# PowerSupply.net
KiCad netlist of a schematic drawn in Altium Designer
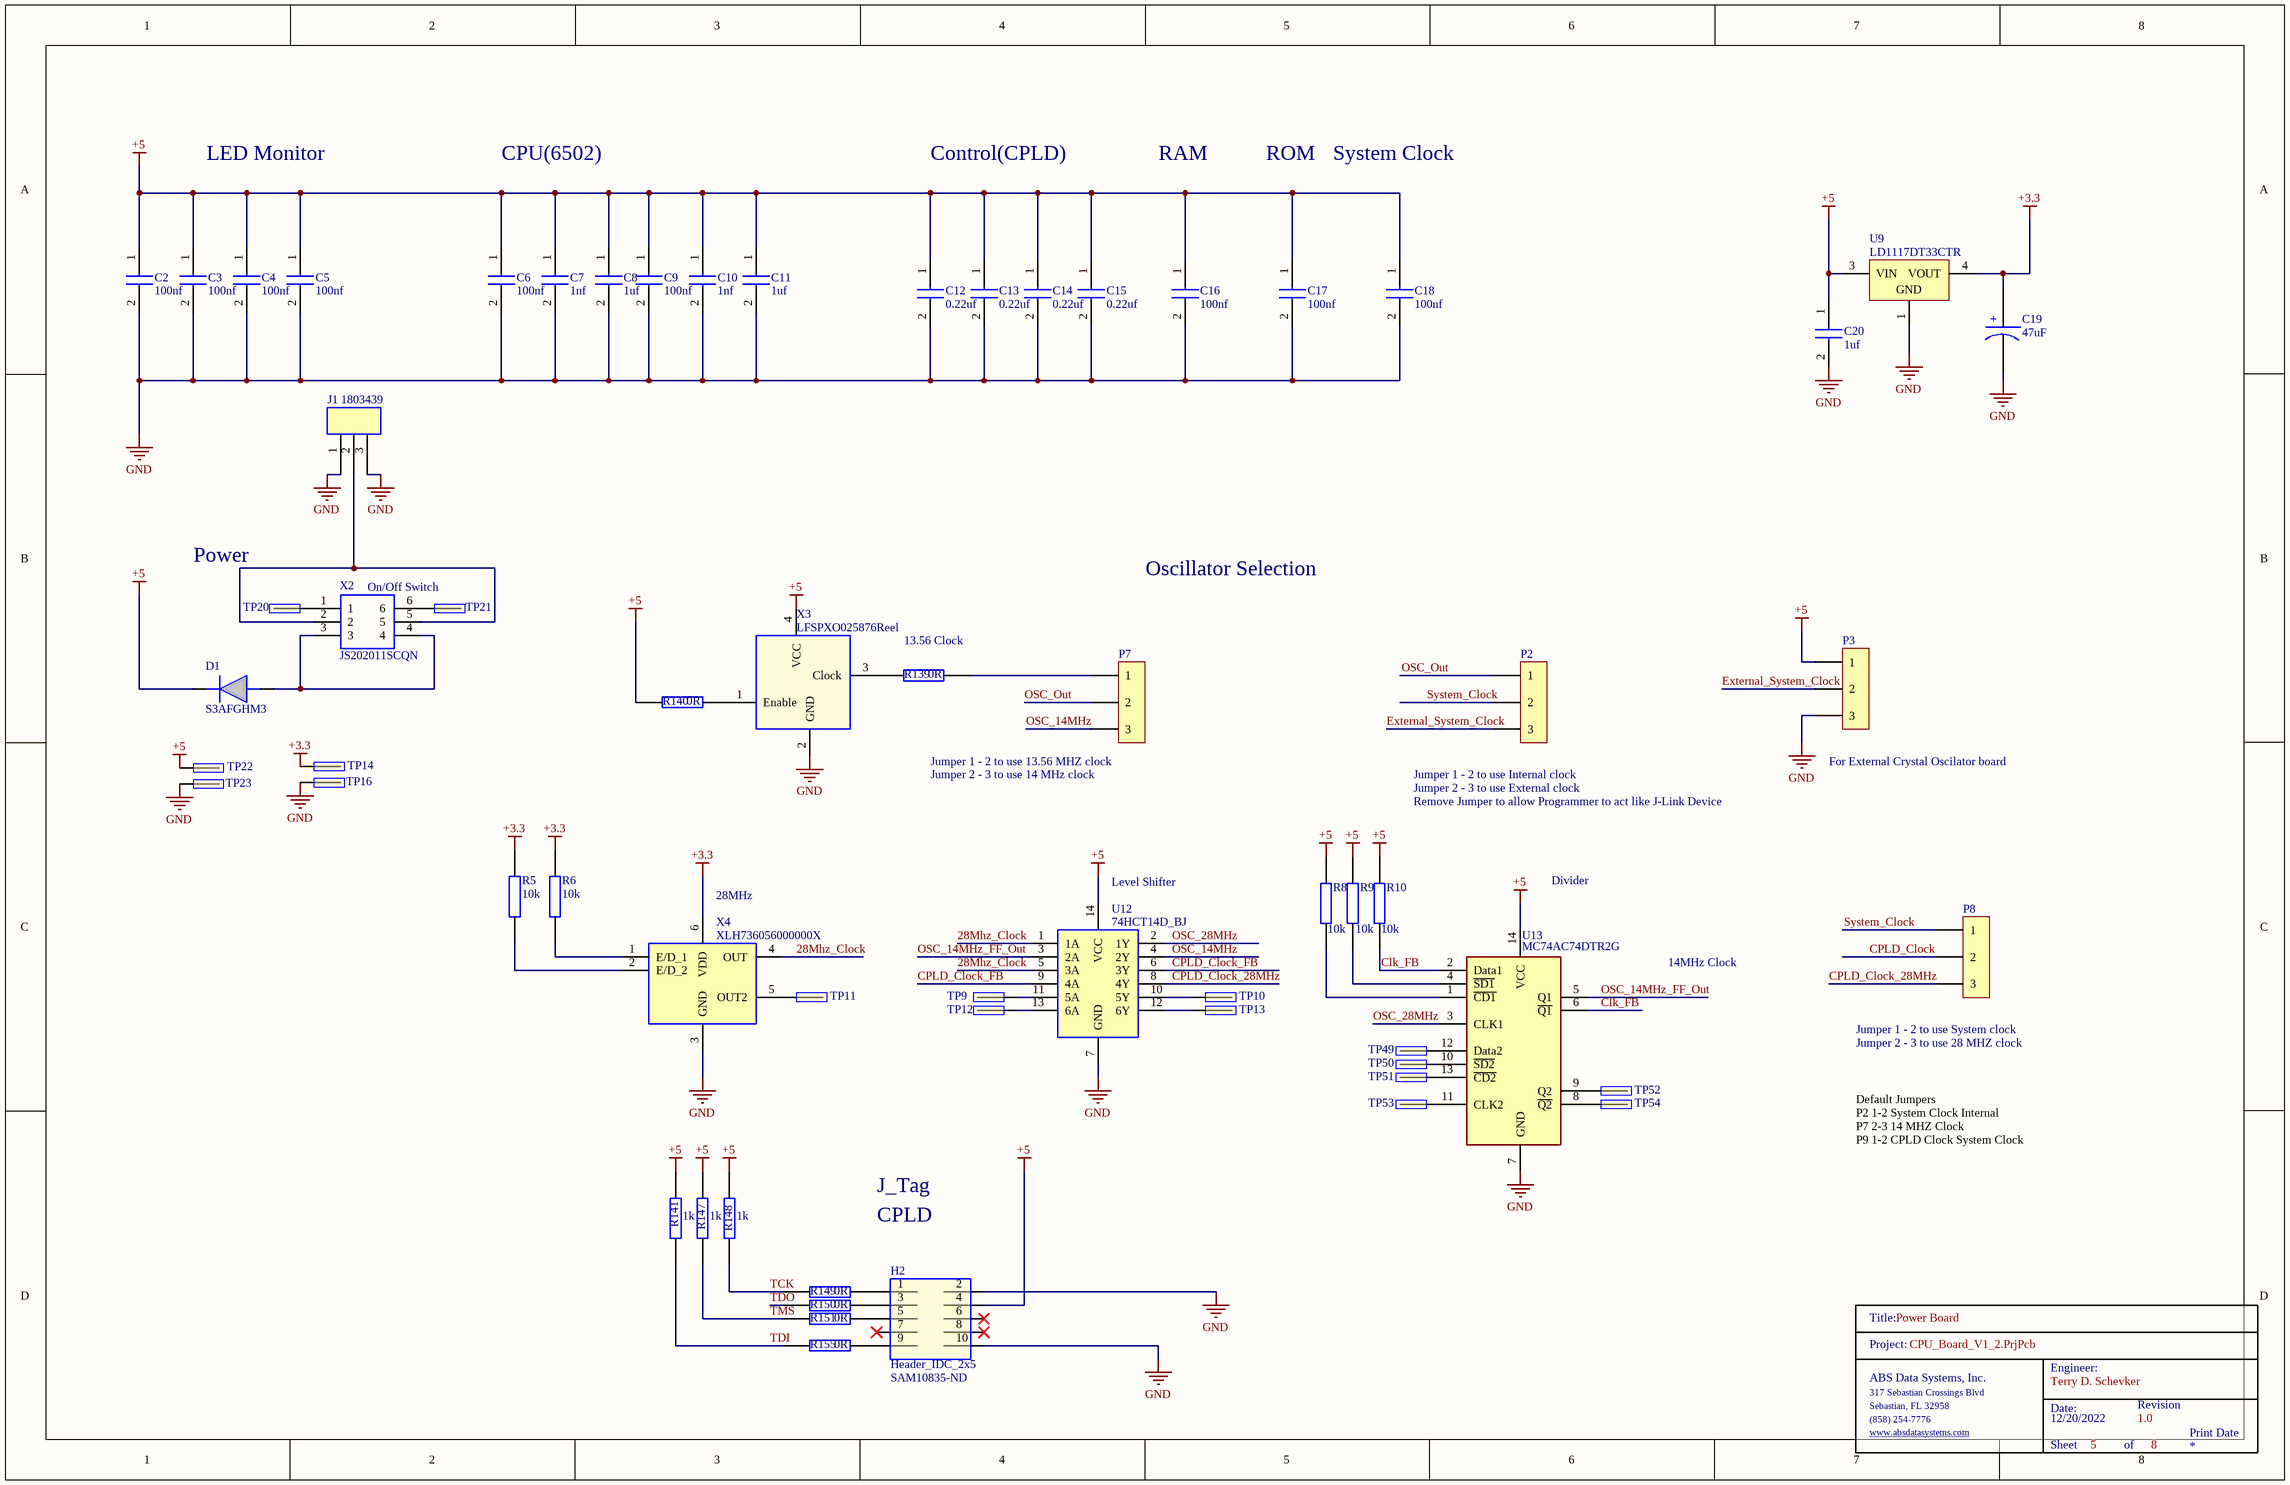
[diagram p0: PowerSupply.SchDoc]

(export (version "E")
  (design (tool "Eeschema 10.0.6"))
  (components
    (comp (ref "C2")
      (value "100nf")
      (footprint "0603")
      (description "Samsung Electro-Mechanics 0603 100nf")
      (libsource (lib "Capacitors") (part "CL10B104JB8NNNC"))
    )
    (comp (ref "C3")
      (value "100nf")
      (footprint "0603")
      (description "Samsung Electro-Mechanics 0603 100nf")
      (libsource (lib "Capacitors") (part "CL10B104JB8NNNC"))
    )
    (comp (ref "C4")
      (value "100nf")
      (footprint "0603")
      (description "Samsung Electro-Mechanics 0603 100nf")
      (libsource (lib "Capacitors") (part "CL10B104JB8NNNC"))
    )
    (comp (ref "C5")
      (value "100nf")
      (footprint "0603")
      (description "Samsung Electro-Mechanics 0603 100nf")
      (libsource (lib "Capacitors") (part "CL10B104JB8NNNC"))
    )
    (comp (ref "C6")
      (value "100nf")
      (footprint "0603")
      (description "Samsung Electro-Mechanics 0603 100nf")
      (libsource (lib "Capacitors") (part "CL10B104JB8NNNC"))
    )
    (comp (ref "C7")
      (value "1nf")
      (footprint "0603")
      (description "Samsung Electro-Mechanics 0603 1nf")
      (libsource (lib "Capacitors") (part "CL10B102KB8NNNL"))
    )
    (comp (ref "C8")
      (value "1uf")
      (footprint "0603")
      (description "Samsung Electro-Mechanics 0603 1uf")
      (libsource (lib "Capacitors") (part "CL10B105KA8NNNL"))
    )
    (comp (ref "C9")
      (value "100nf")
      (footprint "0603")
      (description "Samsung Electro-Mechanics 0603 100nf")
      (libsource (lib "Capacitors") (part "CL10B104JB8NNNC"))
    )
    (comp (ref "C10")
      (value "1nf")
      (footprint "0603")
      (description "Samsung Electro-Mechanics 0603 1nf")
      (libsource (lib "Capacitors") (part "CL10B102KB8NNNL"))
    )
    (comp (ref "C11")
      (value "1uf")
      (footprint "0603")
      (description "Samsung Electro-Mechanics 0603 1uf")
      (libsource (lib "Capacitors") (part "CL10B105KA8NNNL"))
    )
    (comp (ref "C12")
      (value "0.22uf")
      (footprint "0603")
      (description "Samsung Electro-Mechanics 0603 100nf")
      (libsource (lib "Capacitors") (part "CL10B104JB8NNNC"))
    )
    (comp (ref "C13")
      (value "0.22uf")
      (footprint "0603")
      (description "Samsung Electro-Mechanics 0603 100nf")
      (libsource (lib "Capacitors") (part "CL10B104JB8NNNC"))
    )
    (comp (ref "C14")
      (value "0.22uf")
      (footprint "0603")
      (description "Samsung Electro-Mechanics 0603 100nf")
      (libsource (lib "Capacitors") (part "CL10B104JB8NNNC"))
    )
    (comp (ref "C15")
      (value "0.22uf")
      (footprint "0603")
      (description "Samsung Electro-Mechanics 0603 100nf")
      (libsource (lib "Capacitors") (part "CL10B104JB8NNNC"))
    )
    (comp (ref "C16")
      (value "100nf")
      (footprint "0603")
      (description "Samsung Electro-Mechanics 0603 100nf")
      (libsource (lib "Capacitors") (part "CL10B104JB8NNNC"))
    )
    (comp (ref "C17")
      (value "100nf")
      (footprint "0603")
      (description "Samsung Electro-Mechanics 0603 100nf")
      (libsource (lib "Capacitors") (part "CL10B104JB8NNNC"))
    )
    (comp (ref "C18")
      (value "100nf")
      (footprint "0603")
      (description "Samsung Electro-Mechanics 0603 100nf")
      (libsource (lib "Capacitors") (part "CL10B104JB8NNNC"))
    )
    (comp (ref "C19")
      (value "47uF")
      (footprint "CapSMD_6.3x5.8")
      (description "CAP ALUM 47UF 20% 16V SMD")
      (fields
        (field (name "MANUFACTURER") "Nichicon")
        (field (name "MANUFACTURER PART NUMBER") "UUD1C470MCL1GS")
      )
      (libsource (lib "Capacitors") (part "UUD1C470MCL1GS"))
    )
    (comp (ref "C20")
      (value "1uf")
      (footprint "0603")
      (description "Samsung Electro-Mechanics 0603 1uf")
      (libsource (lib "Capacitors") (part "CL10B105KA8NNNL"))
    )
    (comp (ref "D1")
      (value "S3AFGHM3")
      (footprint "SemiConductors:do-221ac")
      (description "Rectifiers VR=400V, IO=3A")
      (fields
        (field (name "MOUSER PART NUMBER") "750-1N4001-G")
        (field (name "MANUFACTURER_PART_NUMBER") "1N4001-G")
      )
      (libsource (lib "SemiConductors") (part "S3AFGHM3/I"))
    )
    (comp (ref "H2")
      (value "Header_IDC_2x5")
      (footprint "HDR2X5")
      (description "10 Pin 2x5 Through Hold IDC Connector")
      (fields
        (field (name "MANUFACTURER") "Samtec")
        (field (name "MANUFACTURER PART NUMBER") "TST-105-01-G-D")
        (field (name "SUPPLIER PART NUMBER 1") "SAM10835-ND")
      )
      (libsource (lib "Misc") (part "Header_IDC_2x5"))
    )
    (comp (ref "J1")
      (value "1803439")
      (footprint "Connectors:1803439")
      (description "Connector")
      (fields (field (name "MOUSER PART NUMBER") "651-1803439"))
      (libsource (lib "Connectors") (part "1803439"))
    )
    (comp (ref "P2")
      (value "MHDR1X3_100")
      (footprint "MHDR1X3_100")
      (description "Header, 3-Pin")
      (fields (field (name "PUBLISHER") "Altium Limited"))
      (libsource (lib "Connectors") (part "MHDR1X3_100"))
    )
    (comp (ref "P3")
      (value "MHDR1X3_100")
      (footprint "MHDR1X3_100")
      (description "Header, 3-Pin")
      (fields (field (name "PUBLISHER") "Altium Limited"))
      (libsource (lib "Connectors") (part "MHDR1X3_100"))
    )
    (comp (ref "P7")
      (value "MHDR1X3_100")
      (footprint "MHDR1X3_100")
      (description "Header, 3-Pin")
      (fields (field (name "PUBLISHER") "Altium Limited"))
      (libsource (lib "Connectors") (part "MHDR1X3_100"))
    )
    (comp (ref "P8")
      (value "MHDR1X3_100")
      (footprint "MHDR1X3_100")
      (description "Header, 3-Pin")
      (fields (field (name "PUBLISHER") "Altium Limited"))
      (libsource (lib "Connectors") (part "MHDR1X3_100"))
    )
    (comp (ref "R5")
      (value "10k")
      (footprint "0603")
      (description "YAGEO 0603 10k ohm")
      (fields
        (field (name "MOUSER PART NUMBER") "603-RC0603JR-070RL")
        (field (name "MANUFACTURER_PART_NUMBER") "RC0603JR-070RL")
      )
      (libsource (lib "Resistors") (part "RC0603JR-0710KL"))
    )
    (comp (ref "R6")
      (value "10k")
      (footprint "0603")
      (description "YAGEO 0603 10k ohm")
      (fields
        (field (name "MOUSER PART NUMBER") "603-RC0603JR-070RL")
        (field (name "MANUFACTURER_PART_NUMBER") "RC0603JR-070RL")
      )
      (libsource (lib "Resistors") (part "RC0603JR-0710KL"))
    )
    (comp (ref "R8")
      (value "10k")
      (footprint "0603")
      (description "YAGEO 0603 10k ohm")
      (fields
        (field (name "MOUSER PART NUMBER") "603-RC0603JR-070RL")
        (field (name "MANUFACTURER_PART_NUMBER") "RC0603JR-070RL")
      )
      (libsource (lib "Resistors") (part "RC0603JR-0710KL"))
    )
    (comp (ref "R9")
      (value "10k")
      (footprint "0603")
      (description "YAGEO 0603 10k ohm")
      (fields
        (field (name "MOUSER PART NUMBER") "603-RC0603JR-070RL")
        (field (name "MANUFACTURER_PART_NUMBER") "RC0603JR-070RL")
      )
      (libsource (lib "Resistors") (part "RC0603JR-0710KL"))
    )
    (comp (ref "R10")
      (value "10k")
      (footprint "0603")
      (description "YAGEO 0603 10k ohm")
      (fields
        (field (name "MOUSER PART NUMBER") "603-RC0603JR-070RL")
        (field (name "MANUFACTURER_PART_NUMBER") "RC0603JR-070RL")
      )
      (libsource (lib "Resistors") (part "RC0603JR-0710KL"))
    )
    (comp (ref "R139")
      (value "0R")
      (footprint "0603")
      (description "YAGEO 0603 0 ohm")
      (fields
        (field (name "MOUSER PART NUMBER") "603-RC0603JR-070RL")
        (field (name "MANUFACTURER_PART_NUMBER") "RC0603JR-070RL")
      )
      (libsource (lib "Resistors") (part "RC0603JR-070RL"))
    )
    (comp (ref "R140")
      (value "0R")
      (footprint "0603")
      (description "YAGEO 0603 0 ohm")
      (fields
        (field (name "MOUSER PART NUMBER") "603-RC0603JR-070RL")
        (field (name "MANUFACTURER_PART_NUMBER") "RC0603JR-070RL")
      )
      (libsource (lib "Resistors") (part "RC0603JR-070RL"))
    )
    (comp (ref "R141")
      (value "1k")
      (footprint "0603")
      (description "YAGEO 0603 1k ohm")
      (fields
        (field (name "MOUSER PART NUMBER") "603-RC0603JR-070RL")
        (field (name "MANUFACTURER_PART_NUMBER") "RC0603JR-070RL")
      )
      (libsource (lib "Resistors") (part "AC0603FR-7W1KL"))
    )
    (comp (ref "R147")
      (value "1k")
      (footprint "0603")
      (description "YAGEO 0603 1k ohm")
      (fields
        (field (name "MOUSER PART NUMBER") "603-RC0603JR-070RL")
        (field (name "MANUFACTURER_PART_NUMBER") "RC0603JR-070RL")
      )
      (libsource (lib "Resistors") (part "AC0603FR-7W1KL"))
    )
    (comp (ref "R148")
      (value "1k")
      (footprint "0603")
      (description "YAGEO 0603 1k ohm")
      (fields
        (field (name "MOUSER PART NUMBER") "603-RC0603JR-070RL")
        (field (name "MANUFACTURER_PART_NUMBER") "RC0603JR-070RL")
      )
      (libsource (lib "Resistors") (part "AC0603FR-7W1KL"))
    )
    (comp (ref "R149")
      (value "0R")
      (footprint "0603")
      (description "YAGEO 0603 0 ohm")
      (fields
        (field (name "MOUSER PART NUMBER") "603-RC0603JR-070RL")
        (field (name "MANUFACTURER_PART_NUMBER") "RC0603JR-070RL")
      )
      (libsource (lib "Resistors") (part "RC0603JR-070RL"))
    )
    (comp (ref "R150")
      (value "0R")
      (footprint "0603")
      (description "YAGEO 0603 0 ohm")
      (fields
        (field (name "MOUSER PART NUMBER") "603-RC0603JR-070RL")
        (field (name "MANUFACTURER_PART_NUMBER") "RC0603JR-070RL")
      )
      (libsource (lib "Resistors") (part "RC0603JR-070RL"))
    )
    (comp (ref "R151")
      (value "0R")
      (footprint "0603")
      (description "YAGEO 0603 0 ohm")
      (fields
        (field (name "MOUSER PART NUMBER") "603-RC0603JR-070RL")
        (field (name "MANUFACTURER_PART_NUMBER") "RC0603JR-070RL")
      )
      (libsource (lib "Resistors") (part "RC0603JR-070RL"))
    )
    (comp (ref "R155")
      (value "0R")
      (footprint "0603")
      (description "YAGEO 0603 0 ohm")
      (fields
        (field (name "MOUSER PART NUMBER") "603-RC0603JR-070RL")
        (field (name "MANUFACTURER_PART_NUMBER") "RC0603JR-070RL")
      )
      (libsource (lib "Resistors") (part "RC0603JR-070RL"))
    )
    (comp (ref "TitleBlock_3") (value "TitleBlock") (libsource (lib "Misc") (part "TitleBlock")))
    (comp (ref "TP9")
      (value "~")
      (footprint "TP")
      (fields
        (field (name "MANUFACTURER") "Samtec")
        (field (name "MANUFACTURER PART NUMBER") "TST-105-01-G-D")
      )
      (libsource (lib "Misc") (part "TP"))
    )
    (comp (ref "TP10")
      (value "TP")
      (footprint "TP")
      (fields
        (field (name "MANUFACTURER") "Samtec")
        (field (name "MANUFACTURER PART NUMBER") "TST-105-01-G-D")
      )
      (libsource (lib "") (part "TP_1"))
    )
    (comp (ref "TP11")
      (value "TP")
      (footprint "TP")
      (fields
        (field (name "MANUFACTURER") "Samtec")
        (field (name "MANUFACTURER PART NUMBER") "TST-105-01-G-D")
      )
      (libsource (lib "") (part "TP_1"))
    )
    (comp (ref "TP12")
      (value "~")
      (footprint "TP")
      (fields
        (field (name "MANUFACTURER") "Samtec")
        (field (name "MANUFACTURER PART NUMBER") "TST-105-01-G-D")
      )
      (libsource (lib "Misc") (part "TP"))
    )
    (comp (ref "TP13")
      (value "TP")
      (footprint "TP")
      (fields
        (field (name "MANUFACTURER") "Samtec")
        (field (name "MANUFACTURER PART NUMBER") "TST-105-01-G-D")
      )
      (libsource (lib "") (part "TP_1"))
    )
    (comp (ref "TP14")
      (value "TP")
      (footprint "TP")
      (fields
        (field (name "MANUFACTURER") "Samtec")
        (field (name "MANUFACTURER PART NUMBER") "TST-105-01-G-D")
      )
      (libsource (lib "") (part "TP_2"))
    )
    (comp (ref "TP16")
      (value "TP")
      (footprint "TP")
      (fields
        (field (name "MANUFACTURER") "Samtec")
        (field (name "MANUFACTURER PART NUMBER") "TST-105-01-G-D")
      )
      (libsource (lib "") (part "TP_2"))
    )
    (comp (ref "TP20")
      (value "~")
      (footprint "TP")
      (fields
        (field (name "MANUFACTURER") "Samtec")
        (field (name "MANUFACTURER PART NUMBER") "TST-105-01-G-D")
      )
      (libsource (lib "Misc") (part "TP"))
    )
    (comp (ref "TP21")
      (value "~")
      (footprint "TP")
      (fields
        (field (name "MANUFACTURER") "Samtec")
        (field (name "MANUFACTURER PART NUMBER") "TST-105-01-G-D")
      )
      (libsource (lib "") (part "TP_2"))
    )
    (comp (ref "TP22")
      (value "TP")
      (footprint "TP")
      (fields
        (field (name "MANUFACTURER") "Samtec")
        (field (name "MANUFACTURER PART NUMBER") "TST-105-01-G-D")
      )
      (libsource (lib "") (part "TP_2"))
    )
    (comp (ref "TP23")
      (value "TP")
      (footprint "TP")
      (fields
        (field (name "MANUFACTURER") "Samtec")
        (field (name "MANUFACTURER PART NUMBER") "TST-105-01-G-D")
      )
      (libsource (lib "") (part "TP_2"))
    )
    (comp (ref "TP49")
      (value "TP")
      (footprint "TP")
      (fields
        (field (name "MANUFACTURER") "Samtec")
        (field (name "MANUFACTURER PART NUMBER") "TST-105-01-G-D")
      )
      (libsource (lib "Misc") (part "TP"))
    )
    (comp (ref "TP50")
      (value "TP")
      (footprint "TP")
      (fields
        (field (name "MANUFACTURER") "Samtec")
        (field (name "MANUFACTURER PART NUMBER") "TST-105-01-G-D")
      )
      (libsource (lib "Misc") (part "TP"))
    )
    (comp (ref "TP51")
      (value "TP")
      (footprint "TP")
      (fields
        (field (name "MANUFACTURER") "Samtec")
        (field (name "MANUFACTURER PART NUMBER") "TST-105-01-G-D")
      )
      (libsource (lib "Misc") (part "TP"))
    )
    (comp (ref "TP52")
      (value "TP")
      (footprint "TP")
      (fields
        (field (name "MANUFACTURER") "Samtec")
        (field (name "MANUFACTURER PART NUMBER") "TST-105-01-G-D")
      )
      (libsource (lib "") (part "TP_1"))
    )
    (comp (ref "TP53")
      (value "TP")
      (footprint "TP")
      (fields
        (field (name "MANUFACTURER") "Samtec")
        (field (name "MANUFACTURER PART NUMBER") "TST-105-01-G-D")
      )
      (libsource (lib "Misc") (part "TP"))
    )
    (comp (ref "TP54")
      (value "TP")
      (footprint "TP")
      (fields
        (field (name "MANUFACTURER") "Samtec")
        (field (name "MANUFACTURER PART NUMBER") "TST-105-01-G-D")
      )
      (libsource (lib "") (part "TP_1"))
    )
    (comp (ref "U9")
      (value "LD1117DT33CTR")
      (footprint "TO-252_N")
      (description "3.3V Voltage Regulator SMD")
      (libsource (lib "Misc") (part "PM-REG-LD1117-SOT3"))
    )
    (comp (ref "U12")
      (value "74HCT14D_BJ")
      (footprint "Logic:SOIC127P600X175-14N")
      (description "Inveter")
      (libsource (lib "Logic") (part "74HCT14D_BJ"))
    )
    (comp (ref "U13")
      (value "MC74AC74DTR2G")
      (footprint "Logic:SOP65P640X120-14N")
      (description "FlipFlop")
      (libsource (lib "Logic") (part "MC74AC74DTR2G"))
    )
    (comp (ref "X2")
      (value "JS202011SCQN")
      (footprint "JS202011SCQN")
      (description "Sub miniature slide switches")
      (fields (field (name "MOUSER PART NUMBER") "611-JS202011SCQN"))
      (libsource (lib "Misc") (part "JS202011SCQN"))
    )
    (comp (ref "X3")
      (value "LFSPXO025876Reel")
      (footprint "LFSPXO025876Reel")
      (description "Standard Clock Oscillators 13.56MHz 5V 100ppm -40C +85C")
      (fields (field (name "MOUSER PART NUMBER") "449-LFSPXO025876REEL"))
      (libsource (lib "Misc") (part "LFSPXO025876Reel"))
    )
    (comp (ref "X4")
      (value "XLH736056000000X")
      (footprint "Misc:XLH736056000000X")
      (description "Crystall Oscillator")
      (libsource (lib "Misc") (part "XLH736056000000X"))
    )
  )
  (nets
    (net (code "1") (name "+3.3") (class "Default")
      (node (ref "C19") (pin "1") (pinfunction "1_1") (pintype "passive"))
      (node (ref "R5") (pin "2") (pinfunction "2_2") (pintype "passive"))
      (node (ref "R6") (pin "2") (pinfunction "2_2") (pintype "passive"))
      (node (ref "TP14") (pin "1") (pinfunction "1_1") (pintype "passive"))
      (node (ref "U9") (pin "4") (pinfunction "VOUT_4") (pintype "power_in"))
      (node (ref "X4") (pin "6") (pinfunction "VDD_6") (pintype "passive"))
    )
    (net (code "2") (name "+5") (class "Default")
      (node (ref "C10") (pin "1") (pinfunction "1_1") (pintype "passive"))
      (node (ref "C11") (pin "1") (pinfunction "1_1") (pintype "passive"))
      (node (ref "C12") (pin "1") (pinfunction "1_1") (pintype "passive"))
      (node (ref "C13") (pin "1") (pinfunction "1_1") (pintype "passive"))
      (node (ref "C14") (pin "1") (pinfunction "1_1") (pintype "passive"))
      (node (ref "C15") (pin "1") (pinfunction "1_1") (pintype "passive"))
      (node (ref "C16") (pin "1") (pinfunction "1_1") (pintype "passive"))
      (node (ref "C17") (pin "1") (pinfunction "1_1") (pintype "passive"))
      (node (ref "C18") (pin "1") (pinfunction "1_1") (pintype "passive"))
      (node (ref "C2") (pin "1") (pinfunction "1_1") (pintype "passive"))
      (node (ref "C20") (pin "1") (pinfunction "1_1") (pintype "passive"))
      (node (ref "C3") (pin "1") (pinfunction "1_1") (pintype "passive"))
      (node (ref "C4") (pin "1") (pinfunction "1_1") (pintype "passive"))
      (node (ref "C5") (pin "1") (pinfunction "1_1") (pintype "passive"))
      (node (ref "C6") (pin "1") (pinfunction "1_1") (pintype "passive"))
      (node (ref "C7") (pin "1") (pinfunction "1_1") (pintype "passive"))
      (node (ref "C8") (pin "1") (pinfunction "1_1") (pintype "passive"))
      (node (ref "C9") (pin "1") (pinfunction "1_1") (pintype "passive"))
      (node (ref "D1") (pin "1") (pinfunction "K_1") (pintype "passive"))
      (node (ref "H2") (pin "4") (pinfunction "4_4") (pintype "passive"))
      (node (ref "P3") (pin "1") (pinfunction "1_1") (pintype "passive"))
      (node (ref "R10") (pin "2") (pinfunction "2_2") (pintype "passive"))
      (node (ref "R140") (pin "1") (pinfunction "1_1") (pintype "passive"))
      (node (ref "R141") (pin "1") (pinfunction "1_1") (pintype "passive"))
      (node (ref "R147") (pin "1") (pinfunction "1_1") (pintype "passive"))
      (node (ref "R148") (pin "1") (pinfunction "1_1") (pintype "passive"))
      (node (ref "R8") (pin "2") (pinfunction "2_2") (pintype "passive"))
      (node (ref "R9") (pin "2") (pinfunction "2_2") (pintype "passive"))
      (node (ref "TP22") (pin "1") (pinfunction "1_1") (pintype "passive"))
      (node (ref "U12") (pin "14") (pinfunction "VCC_14") (pintype "passive"))
      (node (ref "U13") (pin "14") (pinfunction "VCC_14") (pintype "passive"))
      (node (ref "U9") (pin "3") (pinfunction "VIN_3") (pintype "power_in"))
      (node (ref "X3") (pin "4") (pinfunction "VCC_4") (pintype "passive"))
    )
    (net (code "3") (name "/28Mhz_Clock") (class "Default")
      (node (ref "U12") (pin "1") (pinfunction "1A_1") (pintype "passive"))
      (node (ref "U12") (pin "5") (pinfunction "3A_5") (pintype "passive"))
      (node (ref "X4") (pin "4") (pinfunction "OUT_4") (pintype "passive"))
    )
    (net (code "4") (name "/CPLD_Clock") (class "Default")
      (node (ref "P8") (pin "2") (pinfunction "2_2") (pintype "passive"))
    )
    (net (code "5") (name "/CPLD_Clock_28MHz") (class "Default")
      (node (ref "P8") (pin "3") (pinfunction "3_3") (pintype "passive"))
      (node (ref "U12") (pin "8") (pinfunction "4Y_8") (pintype "passive"))
    )
    (net (code "6") (name "/CPLD_Clock_FB") (class "Default")
      (node (ref "U12") (pin "6") (pinfunction "3Y_6") (pintype "passive"))
      (node (ref "U12") (pin "9") (pinfunction "4A_9") (pintype "passive"))
    )
    (net (code "7") (name "/Clk_FB") (class "Default")
      (node (ref "R10") (pin "1") (pinfunction "1_1") (pintype "passive"))
      (node (ref "U13") (pin "2") (pinfunction "Data1_2") (pintype "passive"))
      (node (ref "U13") (pin "6") (pinfunction "~{Q1}_6") (pintype "passive"))
    )
    (net (code "8") (name "/External_System_Clock") (class "Default")
      (node (ref "P2") (pin "3") (pinfunction "3_3") (pintype "passive"))
      (node (ref "P3") (pin "2") (pinfunction "2_2") (pintype "passive"))
    )
    (net (code "9") (name "/OSC_14MHz") (class "Default")
      (node (ref "P7") (pin "3") (pinfunction "3_3") (pintype "passive"))
      (node (ref "U12") (pin "4") (pinfunction "2Y_4") (pintype "passive"))
    )
    (net (code "10") (name "/OSC_14MHz_FF_Out") (class "Default")
      (node (ref "U12") (pin "3") (pinfunction "2A_3") (pintype "passive"))
      (node (ref "U13") (pin "5") (pinfunction "Q1_5") (pintype "passive"))
    )
    (net (code "11") (name "/OSC_28MHz") (class "Default")
      (node (ref "U12") (pin "2") (pinfunction "1Y_2") (pintype "passive"))
      (node (ref "U13") (pin "3") (pinfunction "CLK1_3") (pintype "passive"))
    )
    (net (code "12") (name "/OSC_Out") (class "Default")
      (node (ref "P2") (pin "1") (pinfunction "1_1") (pintype "passive"))
      (node (ref "P7") (pin "2") (pinfunction "2_2") (pintype "passive"))
    )
    (net (code "13") (name "/System_Clock") (class "Default")
      (node (ref "P2") (pin "2") (pinfunction "2_2") (pintype "passive"))
      (node (ref "P8") (pin "1") (pinfunction "1_1") (pintype "passive"))
    )
    (net (code "14") (name "/TCK") (class "Default")
      (node (ref "R148") (pin "2") (pinfunction "2_2") (pintype "passive"))
      (node (ref "R149") (pin "1") (pinfunction "1_1") (pintype "passive"))
    )
    (net (code "15") (name "/TDI") (class "Default")
      (node (ref "R141") (pin "2") (pinfunction "2_2") (pintype "passive"))
      (node (ref "R155") (pin "1") (pinfunction "1_1") (pintype "passive"))
    )
    (net (code "16") (name "/TDO") (class "Default")
      (node (ref "R150") (pin "1") (pinfunction "1_1") (pintype "passive"))
    )
    (net (code "17") (name "/TMS") (class "Default")
      (node (ref "R147") (pin "2") (pinfunction "2_2") (pintype "passive"))
      (node (ref "R151") (pin "1") (pinfunction "1_1") (pintype "passive"))
    )
    (net (code "18") (name "GND") (class "Default")
      (node (ref "C10") (pin "2") (pinfunction "2_2") (pintype "passive"))
      (node (ref "C11") (pin "2") (pinfunction "2_2") (pintype "passive"))
      (node (ref "C12") (pin "2") (pinfunction "2_2") (pintype "passive"))
      (node (ref "C13") (pin "2") (pinfunction "2_2") (pintype "passive"))
      (node (ref "C14") (pin "2") (pinfunction "2_2") (pintype "passive"))
      (node (ref "C15") (pin "2") (pinfunction "2_2") (pintype "passive"))
      (node (ref "C16") (pin "2") (pinfunction "2_2") (pintype "passive"))
      (node (ref "C17") (pin "2") (pinfunction "2_2") (pintype "passive"))
      (node (ref "C18") (pin "2") (pinfunction "2_2") (pintype "passive"))
      (node (ref "C19") (pin "2") (pinfunction "2_2") (pintype "passive"))
      (node (ref "C2") (pin "2") (pinfunction "2_2") (pintype "passive"))
      (node (ref "C20") (pin "2") (pinfunction "2_2") (pintype "passive"))
      (node (ref "C3") (pin "2") (pinfunction "2_2") (pintype "passive"))
      (node (ref "C4") (pin "2") (pinfunction "2_2") (pintype "passive"))
      (node (ref "C5") (pin "2") (pinfunction "2_2") (pintype "passive"))
      (node (ref "C6") (pin "2") (pinfunction "2_2") (pintype "passive"))
      (node (ref "C7") (pin "2") (pinfunction "2_2") (pintype "passive"))
      (node (ref "C8") (pin "2") (pinfunction "2_2") (pintype "passive"))
      (node (ref "C9") (pin "2") (pinfunction "2_2") (pintype "passive"))
      (node (ref "H2") (pin "10") (pinfunction "10_10") (pintype "passive"))
      (node (ref "H2") (pin "2") (pinfunction "2_2") (pintype "passive"))
      (node (ref "J1") (pin "1") (pinfunction "1_1") (pintype "passive"))
      (node (ref "J1") (pin "3") (pinfunction "3_3") (pintype "passive"))
      (node (ref "P3") (pin "3") (pinfunction "3_3") (pintype "passive"))
      (node (ref "TP16") (pin "1") (pinfunction "1_1") (pintype "passive"))
      (node (ref "TP23") (pin "1") (pinfunction "1_1") (pintype "passive"))
      (node (ref "U12") (pin "7") (pinfunction "GND_7") (pintype "passive"))
      (node (ref "U13") (pin "7") (pinfunction "GND_7") (pintype "passive"))
      (node (ref "U9") (pin "1") (pinfunction "GND_1") (pintype "power_in"))
      (node (ref "X3") (pin "2") (pinfunction "GND_2") (pintype "passive"))
      (node (ref "X4") (pin "3") (pinfunction "GND_3") (pintype "passive"))
    )
    (net (code "19") (name "Net-(D1-A)") (class "Default")
      (node (ref "D1") (pin "2") (pinfunction "A_2") (pintype "passive"))
      (node (ref "X2") (pin "3") (pinfunction "3_3") (pintype "passive"))
      (node (ref "X2") (pin "4") (pinfunction "4_4") (pintype "passive"))
    )
    (net (code "20") (name "Net-(H2-Pad1)") (class "Default")
      (node (ref "H2") (pin "1") (pinfunction "1_1") (pintype "passive"))
      (node (ref "R149") (pin "2") (pinfunction "2_2") (pintype "passive"))
    )
    (net (code "21") (name "Net-(H2-Pad3)") (class "Default")
      (node (ref "H2") (pin "3") (pinfunction "3_3") (pintype "passive"))
      (node (ref "R150") (pin "2") (pinfunction "2_2") (pintype "passive"))
    )
    (net (code "22") (name "Net-(H2-Pad5)") (class "Default")
      (node (ref "H2") (pin "5") (pinfunction "5_5") (pintype "passive"))
      (node (ref "R151") (pin "2") (pinfunction "2_2") (pintype "passive"))
    )
    (net (code "23") (name "Net-(H2-Pad9)") (class "Default")
      (node (ref "H2") (pin "9") (pinfunction "9_9") (pintype "passive"))
      (node (ref "R155") (pin "2") (pinfunction "2_2") (pintype "passive"))
    )
    (net (code "24") (name "Net-(J1-Pad2)") (class "Default")
      (node (ref "J1") (pin "2") (pinfunction "2_2") (pintype "passive"))
      (node (ref "X2") (pin "2") (pinfunction "2_2") (pintype "passive"))
      (node (ref "X2") (pin "5") (pinfunction "5_5") (pintype "passive"))
    )
    (net (code "25") (name "Net-(P7-Pad1)") (class "Default")
      (node (ref "P7") (pin "1") (pinfunction "1_1") (pintype "passive"))
      (node (ref "R139") (pin "2") (pinfunction "2_2") (pintype "passive"))
    )
    (net (code "26") (name "Net-(TP20-Pad1)") (class "Default")
      (node (ref "TP20") (pin "1") (pinfunction "1_1") (pintype "passive"))
      (node (ref "X2") (pin "1") (pinfunction "1_1") (pintype "passive"))
    )
    (net (code "27") (name "Net-(TP21-Pad1)") (class "Default")
      (node (ref "TP21") (pin "1") (pinfunction "1_1") (pintype "passive"))
      (node (ref "X2") (pin "6") (pinfunction "6_6") (pintype "passive"))
    )
    (net (code "28") (name "Net-(U12-5A)") (class "Default")
      (node (ref "TP9") (pin "1") (pinfunction "1_1") (pintype "passive"))
      (node (ref "U12") (pin "11") (pinfunction "5A_11") (pintype "passive"))
    )
    (net (code "29") (name "Net-(U12-5Y)") (class "Default")
      (node (ref "TP10") (pin "1") (pinfunction "1_1") (pintype "passive"))
      (node (ref "U12") (pin "10") (pinfunction "5Y_10") (pintype "passive"))
    )
    (net (code "30") (name "Net-(U12-6A)") (class "Default")
      (node (ref "TP12") (pin "1") (pinfunction "1_1") (pintype "passive"))
      (node (ref "U12") (pin "13") (pinfunction "6A_13") (pintype "passive"))
    )
    (net (code "31") (name "Net-(U12-6Y)") (class "Default")
      (node (ref "TP13") (pin "1") (pinfunction "1_1") (pintype "passive"))
      (node (ref "U12") (pin "12") (pinfunction "6Y_12") (pintype "passive"))
    )
    (net (code "32") (name "Net-(U13-CLK2)") (class "Default")
      (node (ref "TP53") (pin "1") (pinfunction "1_1") (pintype "passive"))
      (node (ref "U13") (pin "11") (pinfunction "CLK2_11") (pintype "passive"))
    )
    (net (code "33") (name "Net-(U13-Data2)") (class "Default")
      (node (ref "TP49") (pin "1") (pinfunction "1_1") (pintype "passive"))
      (node (ref "U13") (pin "12") (pinfunction "Data2_12") (pintype "passive"))
    )
    (net (code "34") (name "Net-(U13-Q2)") (class "Default")
      (node (ref "TP52") (pin "1") (pinfunction "1_1") (pintype "passive"))
      (node (ref "U13") (pin "9") (pinfunction "Q2_9") (pintype "passive"))
    )
    (net (code "35") (name "Net-(U13-~{CD1})") (class "Default")
      (node (ref "R8") (pin "1") (pinfunction "1_1") (pintype "passive"))
      (node (ref "U13") (pin "1") (pinfunction "~{CD1}_1") (pintype "passive"))
    )
    (net (code "36") (name "Net-(U13-~{CD2})") (class "Default")
      (node (ref "TP51") (pin "1") (pinfunction "1_1") (pintype "passive"))
      (node (ref "U13") (pin "13") (pinfunction "~{CD2}_13") (pintype "passive"))
    )
    (net (code "37") (name "Net-(U13-~{Q2})") (class "Default")
      (node (ref "TP54") (pin "1") (pinfunction "1_1") (pintype "passive"))
      (node (ref "U13") (pin "8") (pinfunction "~{Q2}_8") (pintype "passive"))
    )
    (net (code "38") (name "Net-(U13-~{SD1})") (class "Default")
      (node (ref "R9") (pin "1") (pinfunction "1_1") (pintype "passive"))
      (node (ref "U13") (pin "4") (pinfunction "~{SD1}_4") (pintype "passive"))
    )
    (net (code "39") (name "Net-(U13-~{SD2})") (class "Default")
      (node (ref "TP50") (pin "1") (pinfunction "1_1") (pintype "passive"))
      (node (ref "U13") (pin "10") (pinfunction "~{SD2}_10") (pintype "passive"))
    )
    (net (code "40") (name "Net-(X3-Clock)") (class "Default")
      (node (ref "R139") (pin "1") (pinfunction "1_1") (pintype "passive"))
      (node (ref "X3") (pin "3") (pinfunction "Clock_3") (pintype "passive"))
    )
    (net (code "41") (name "Net-(X3-Enable)") (class "Default")
      (node (ref "R140") (pin "2") (pinfunction "2_2") (pintype "passive"))
      (node (ref "X3") (pin "1") (pinfunction "Enable_1") (pintype "passive"))
    )
    (net (code "42") (name "Net-(X4-E{slash}D_1)") (class "Default")
      (node (ref "R6") (pin "1") (pinfunction "1_1") (pintype "passive"))
      (node (ref "X4") (pin "1") (pinfunction "E/D_1_1") (pintype "passive"))
    )
    (net (code "43") (name "Net-(X4-E{slash}D_2)") (class "Default")
      (node (ref "R5") (pin "1") (pinfunction "1_1") (pintype "passive"))
      (node (ref "X4") (pin "2") (pinfunction "E/D_2_2") (pintype "passive"))
    )
    (net (code "44") (name "Net-(X4-OUT2)") (class "Default")
      (node (ref "TP11") (pin "1") (pinfunction "1_1") (pintype "passive"))
      (node (ref "X4") (pin "5") (pinfunction "OUT2_5") (pintype "passive"))
    )
    (net (code "45") (name "unconnected-(H2-Pad6)") (class "Default")
      (node (ref "H2") (pin "6") (pinfunction "6_6") (pintype "passive+no_connect"))
    )
    (net (code "46") (name "unconnected-(H2-Pad7)") (class "Default")
      (node (ref "H2") (pin "7") (pinfunction "7_7") (pintype "passive+no_connect"))
    )
    (net (code "47") (name "unconnected-(H2-Pad8)") (class "Default")
      (node (ref "H2") (pin "8") (pinfunction "8_8") (pintype "passive+no_connect"))
    )
  )
)
